# bendor.net
KiCad netlist of a schematic drawn in EAGLE
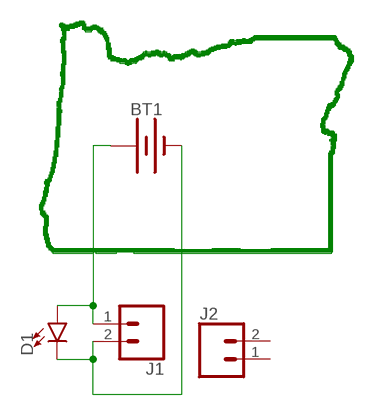
[diagram p0: schematic, sheet 1]

(export (version "E")
  (design (tool "Eeschema 10.0.6"))
  (components
    (comp (ref "BT1")
      (value "BATTERY-20MM_SMD_4LEGS")
      (footprint "eagle-import:BATTCON_20MM_4LEGS")
      (libsource (lib "eagle-import") (part "BATTERY-20MM_SMD_4LEGS"))
    )
    (comp (ref "D1")
      (value "LED3MM")
      (footprint "eagle-import:LED_3MM")
      (libsource (lib "eagle-import") (part "LED3MM"))
    )
    (comp (ref "J1")
      (value "CONN_02LOCK")
      (footprint "eagle-import:1X02_LOCK")
      (libsource (lib "eagle-import") (part "CONN_02LOCK"))
    )
    (comp (ref "J2")
      (value "CONN_02LOCK")
      (footprint "eagle-import:1X02_LOCK")
      (libsource (lib "eagle-import") (part "CONN_02LOCK"))
    )
    (comp (ref "U$1")
      (value "OREGON")
      (footprint "eagle-import:OREGON")
      (libsource (lib "eagle-import") (part "OREGON"))
    )
  )
  (nets
    (net (code "1") (name "Net-(BT1-+-PadPOSITIVE@1)") (class "Default")
      (node (ref "BT1") (pin "POSITIVE@1") (pinfunction "+_POSITIVE@1") (pintype "power_in"))
      (node (ref "BT1") (pin "POSITIVE@2") (pinfunction "+_POSITIVE@2") (pintype "power_in"))
      (node (ref "BT1") (pin "POSITIVE@3") (pinfunction "+_POSITIVE@3") (pintype "power_in"))
      (node (ref "BT1") (pin "POSITIVE@4") (pinfunction "+_POSITIVE@4") (pintype "power_in"))
      (node (ref "D1") (pin "A") (pinfunction "A_A") (pintype "passive"))
      (node (ref "J1") (pin "1") (pinfunction "1_1") (pintype "passive"))
    )
    (net (code "2") (name "Net-(BT1--)") (class "Default")
      (node (ref "BT1") (pin "NEGATIVE") (pinfunction "-_NEGATIVE") (pintype "power_in"))
      (node (ref "D1") (pin "K") (pinfunction "C_K") (pintype "passive"))
      (node (ref "J1") (pin "2") (pinfunction "2_2") (pintype "passive"))
    )
    (net (code "3") (name "unconnected-(J2-Pad1)") (class "Default")
      (node (ref "J2") (pin "1") (pinfunction "1_1") (pintype "passive"))
    )
    (net (code "4") (name "unconnected-(J2-Pad2)") (class "Default")
      (node (ref "J2") (pin "2") (pinfunction "2_2") (pintype "passive"))
    )
  )
)
